# FT231-Breakout-v1_0.net
KiCad netlist of a schematic drawn in EAGLE
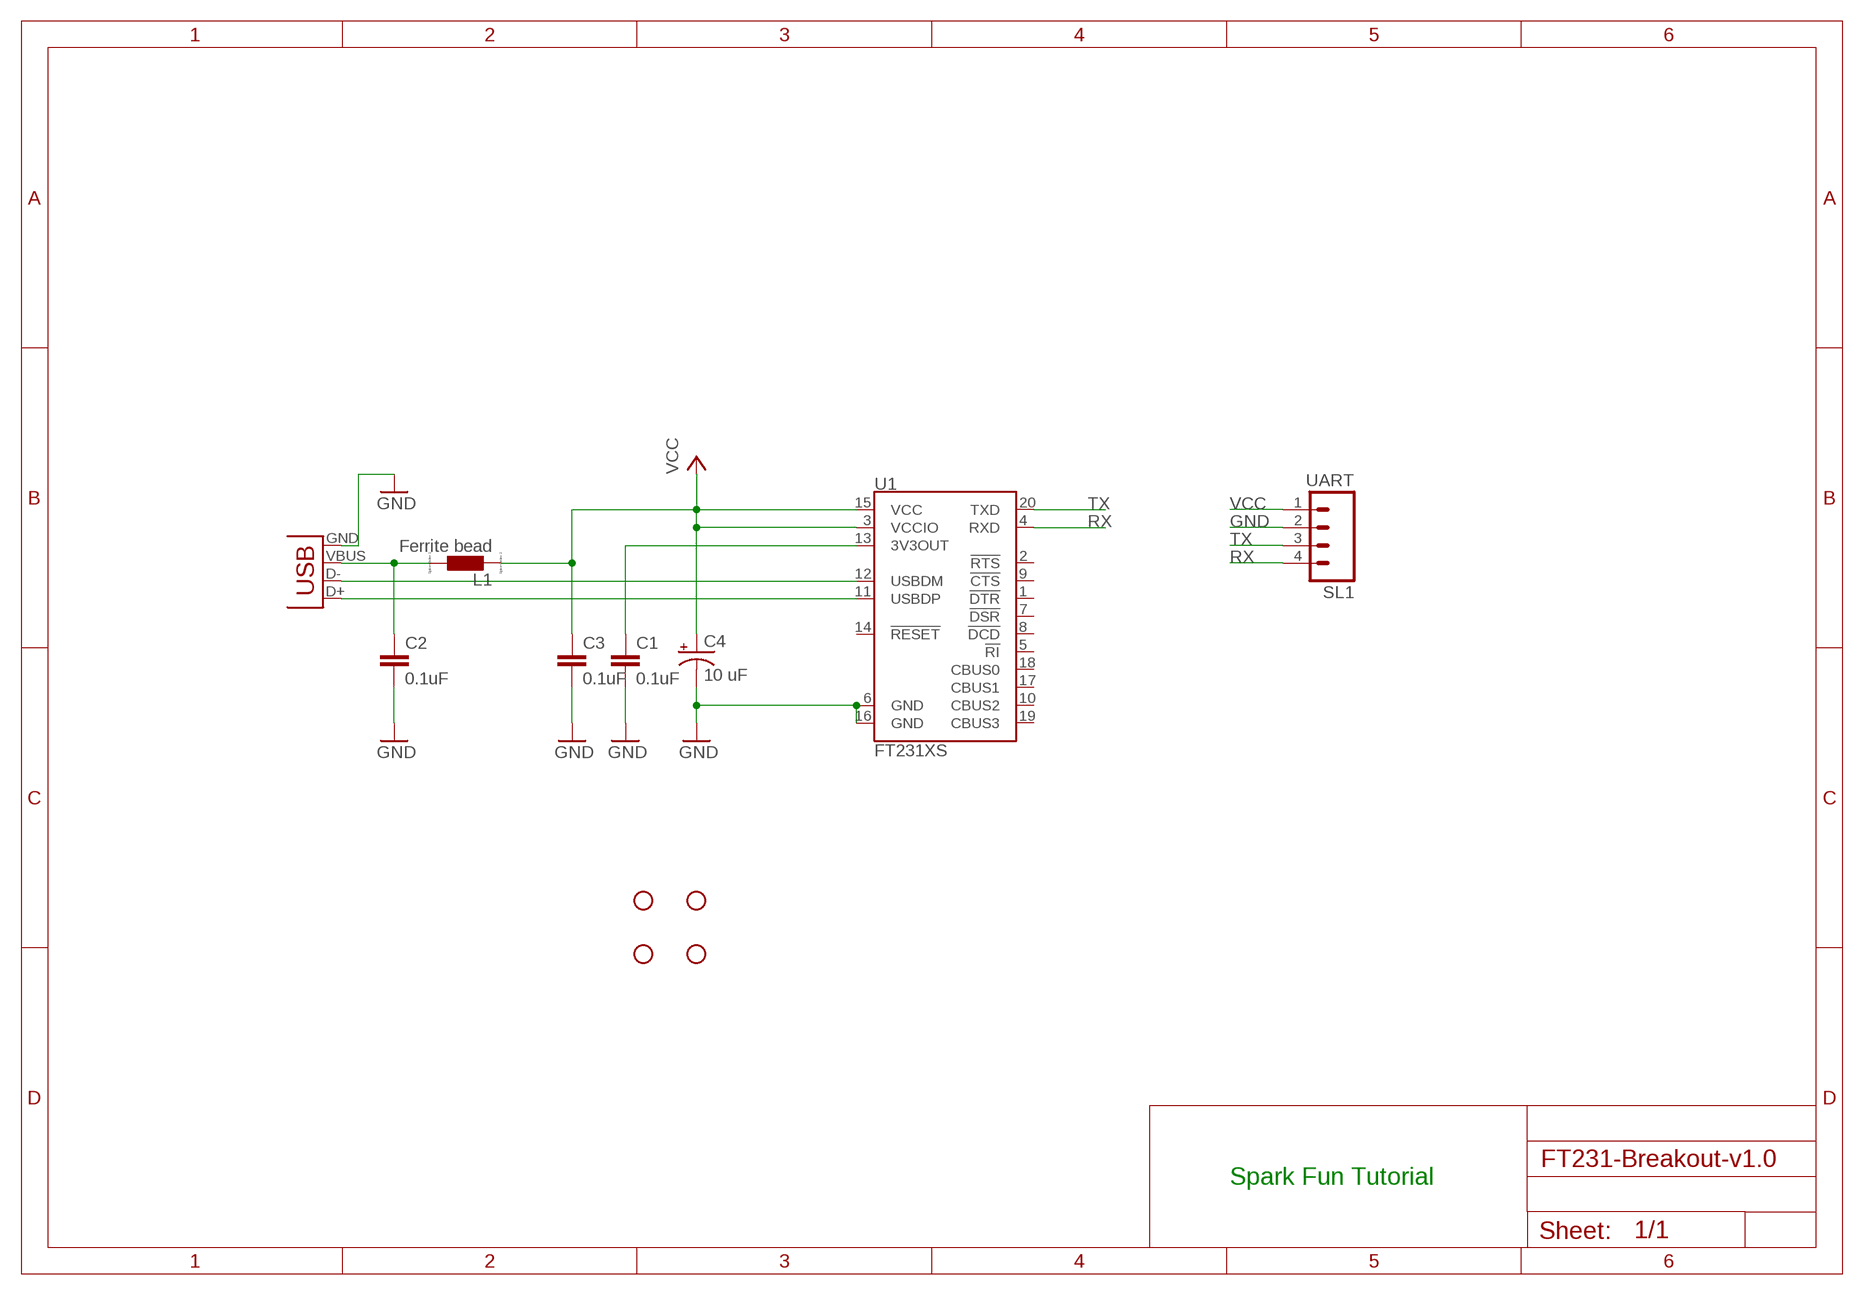
[diagram p0: schematic, sheet 1]

(export (version "E")
  (design (tool "Eeschema 10.0.6"))
  (components
    (comp (ref "C1")
      (value "0.1uF")
      (footprint "eagle-import:0603-CAP")
      (libsource (lib "eagle-import") (part "0.1UF-25V-5%(0603)"))
    )
    (comp (ref "C2")
      (value "0.1uF")
      (footprint "eagle-import:0603-CAP")
      (libsource (lib "eagle-import") (part "0.1UF-25V-5%(0603)"))
    )
    (comp (ref "C3")
      (value "0.1uF")
      (footprint "eagle-import:0603-CAP")
      (libsource (lib "eagle-import") (part "0.1UF-25V-5%(0603)"))
    )
    (comp (ref "C4")
      (value "10 uF")
      (footprint "eagle-import:EIA3216")
      (libsource (lib "eagle-import") (part "CAP_POL1206"))
    )
    (comp (ref "JP1")
      (value "USB-B")
      (footprint "eagle-import:USB-B-PTH")
      (libsource (lib "eagle-import") (part "USBPTH"))
    )
    (comp (ref "L1")
      (value "Ferrite bead")
      (footprint "eagle-import:L1812")
      (libsource (lib "eagle-import") (part "L"))
    )
    (comp (ref "SL1")
      (value "UART")
      (footprint "eagle-import:04P")
      (libsource (lib "eagle-import") (part "M04"))
    )
    (comp (ref "STANDOFF1")
      (value "STAND-OFF")
      (footprint "eagle-import:STAND-OFF")
      (libsource (lib "eagle-import") (part "STAND-OFF"))
    )
    (comp (ref "STANDOFF2")
      (value "STAND-OFF")
      (footprint "eagle-import:STAND-OFF")
      (libsource (lib "eagle-import") (part "STAND-OFF"))
    )
    (comp (ref "STANDOFF3")
      (value "STAND-OFF")
      (footprint "eagle-import:STAND-OFF")
      (libsource (lib "eagle-import") (part "STAND-OFF"))
    )
    (comp (ref "STANDOFF4")
      (value "STAND-OFF")
      (footprint "eagle-import:STAND-OFF")
      (libsource (lib "eagle-import") (part "STAND-OFF"))
    )
    (comp (ref "U1")
      (value "FT231XS")
      (footprint "eagle-import:SSOP20_L")
      (libsource (lib "eagle-import") (part "FT231XS"))
    )
  )
  (nets
    (net (code "1") (name "/RX") (class "Default")
      (node (ref "SL1") (pin "4") (pinfunction "4_4") (pintype "passive"))
      (node (ref "U1") (pin "4") (pinfunction "RXD_4") (pintype "bidirectional"))
    )
    (net (code "2") (name "/TX") (class "Default")
      (node (ref "SL1") (pin "3") (pinfunction "3_3") (pintype "passive"))
      (node (ref "U1") (pin "20") (pinfunction "TXD_20") (pintype "bidirectional"))
    )
    (net (code "3") (name "GND") (class "Default")
      (node (ref "C1") (pin "2") (pinfunction "2_2") (pintype "passive"))
      (node (ref "C2") (pin "2") (pinfunction "2_2") (pintype "passive"))
      (node (ref "C3") (pin "2") (pinfunction "2_2") (pintype "passive"))
      (node (ref "C4") (pin "C") (pinfunction "-_C") (pintype "passive"))
      (node (ref "JP1") (pin "GND") (pinfunction "GND_GND") (pintype "bidirectional"))
      (node (ref "SL1") (pin "2") (pinfunction "2_2") (pintype "passive"))
      (node (ref "U1") (pin "16") (pinfunction "GND_16") (pintype "bidirectional"))
      (node (ref "U1") (pin "6") (pinfunction "GND_6") (pintype "bidirectional"))
    )
    (net (code "4") (name "Net-(C2-Pad1)") (class "Default")
      (node (ref "C2") (pin "1") (pinfunction "1_1") (pintype "passive"))
      (node (ref "JP1") (pin "VBUS") (pinfunction "VBUS_VBUS") (pintype "bidirectional"))
      (node (ref "L1") (pin "1") (pinfunction "1_1") (pintype "passive"))
    )
    (net (code "5") (name "Net-(U1-3V3OUT)") (class "Default")
      (node (ref "C1") (pin "1") (pinfunction "1_1") (pintype "passive"))
      (node (ref "U1") (pin "13") (pinfunction "3V3OUT_13") (pintype "bidirectional"))
    )
    (net (code "6") (name "Net-(U1-USBDM)") (class "Default")
      (node (ref "JP1") (pin "D-") (pinfunction "D-_D-") (pintype "bidirectional"))
      (node (ref "U1") (pin "12") (pinfunction "USBDM_12") (pintype "bidirectional"))
    )
    (net (code "7") (name "Net-(U1-USBDP)") (class "Default")
      (node (ref "JP1") (pin "D+") (pinfunction "D+_D+") (pintype "bidirectional"))
      (node (ref "U1") (pin "11") (pinfunction "USBDP_11") (pintype "bidirectional"))
    )
    (net (code "8") (name "VCC") (class "Default")
      (node (ref "C3") (pin "1") (pinfunction "1_1") (pintype "passive"))
      (node (ref "C4") (pin "A") (pinfunction "+_A") (pintype "passive"))
      (node (ref "L1") (pin "2") (pinfunction "2_2") (pintype "passive"))
      (node (ref "SL1") (pin "1") (pinfunction "1_1") (pintype "passive"))
      (node (ref "U1") (pin "15") (pinfunction "VCC_15") (pintype "bidirectional"))
      (node (ref "U1") (pin "3") (pinfunction "VCCIO_3") (pintype "bidirectional"))
    )
    (net (code "9") (name "unconnected-(U1-CBUS0-Pad18)") (class "Default")
      (node (ref "U1") (pin "18") (pinfunction "CBUS0_18") (pintype "bidirectional"))
    )
    (net (code "10") (name "unconnected-(U1-CBUS1-Pad17)") (class "Default")
      (node (ref "U1") (pin "17") (pinfunction "CBUS1_17") (pintype "bidirectional"))
    )
    (net (code "11") (name "unconnected-(U1-CBUS2-Pad10)") (class "Default")
      (node (ref "U1") (pin "10") (pinfunction "CBUS2_10") (pintype "bidirectional"))
    )
    (net (code "12") (name "unconnected-(U1-CBUS3-Pad19)") (class "Default")
      (node (ref "U1") (pin "19") (pinfunction "CBUS3_19") (pintype "bidirectional"))
    )
    (net (code "13") (name "unconnected-(U1-~{CTS}-Pad9)") (class "Default")
      (node (ref "U1") (pin "9") (pinfunction "~{CTS}_9") (pintype "bidirectional"))
    )
    (net (code "14") (name "unconnected-(U1-~{DCD}-Pad8)") (class "Default")
      (node (ref "U1") (pin "8") (pinfunction "~{DCD}_8") (pintype "bidirectional"))
    )
    (net (code "15") (name "unconnected-(U1-~{DSR}-Pad7)") (class "Default")
      (node (ref "U1") (pin "7") (pinfunction "~{DSR}_7") (pintype "bidirectional"))
    )
    (net (code "16") (name "unconnected-(U1-~{DTR}-Pad1)") (class "Default")
      (node (ref "U1") (pin "1") (pinfunction "~{DTR}_1") (pintype "bidirectional"))
    )
    (net (code "17") (name "unconnected-(U1-~{RESET}-Pad14)") (class "Default")
      (node (ref "U1") (pin "14") (pinfunction "~{RESET}_14") (pintype "bidirectional"))
    )
    (net (code "18") (name "unconnected-(U1-~{RI}-Pad5)") (class "Default")
      (node (ref "U1") (pin "5") (pinfunction "~{RI}_5") (pintype "bidirectional"))
    )
    (net (code "19") (name "unconnected-(U1-~{RTS}-Pad2)") (class "Default")
      (node (ref "U1") (pin "2") (pinfunction "~{RTS}_2") (pintype "bidirectional"))
    )
  )
)
